# ice_header_adapter_pcb.net
KiCad netlist of a schematic drawn in EAGLE
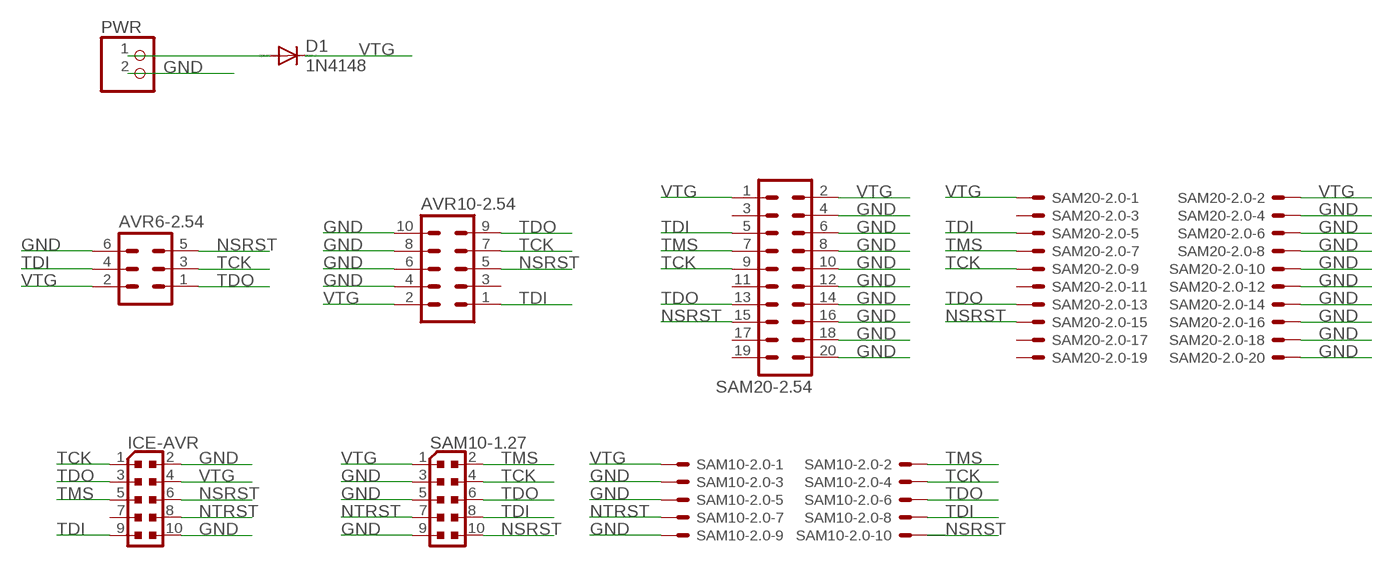
[diagram p0: schematic, sheet 1]

(export (version "E")
  (design (tool "Eeschema 10.0.6"))
  (components
    (comp (ref "AVR6-2.54")
      (value "ML6")
      (footprint "eagle-import:ML6")
      (libsource (lib "eagle-import") (part "ML6"))
    )
    (comp (ref "AVR10-2.54")
      (value "ML10")
      (footprint "eagle-import:ML10")
      (libsource (lib "eagle-import") (part "ML10"))
    )
    (comp (ref "D1")
      (value "1N4148")
      (footprint "eagle-import:DO35-7")
      (libsource (lib "eagle-import") (part "1N4148DO35-7"))
    )
    (comp (ref "ICE-AVR")
      (value "PINHEAD_PINHD-2X5PASSO127")
      (footprint "eagle-import:PINHEAD_2X05_127")
      (libsource (lib "eagle-import") (part "PINHEAD_PINHD-2X5PASSO127"))
    )
    (comp (ref "PWR")
      (value "PINHD-1X2/90")
      (footprint "eagle-import:1X02_90")
      (libsource (lib "eagle-import") (part "PINHD-1X2/90"))
    )
    (comp (ref "SAM10-1.27")
      (value "PINHEAD_PINHD-2X5PASSO127")
      (footprint "eagle-import:PINHEAD_2X05_127")
      (libsource (lib "eagle-import") (part "PINHEAD_PINHD-2X5PASSO127"))
    )
    (comp (ref "SAM10-2.0")
      (value "87758-1016")
      (footprint "eagle-import:87758-1016")
      (fields (field (name "MF") "MOLEX"))
      (libsource (lib "eagle-import") (part "87758-1016"))
    )
    (comp (ref "SAM20-2.0")
      (value "87758-2016")
      (footprint "eagle-import:87758-2016")
      (libsource (lib "eagle-import") (part "87758-2016"))
    )
    (comp (ref "SAM20-2.54")
      (value "ML20")
      (footprint "eagle-import:ML20")
      (libsource (lib "eagle-import") (part "ML20"))
    )
  )
  (nets
    (net (code "1") (name "/GND") (class "Default")
      (node (ref "AVR10-2.54") (pin "10") (pinfunction "10_10") (pintype "passive"))
      (node (ref "AVR10-2.54") (pin "4") (pinfunction "4_4") (pintype "passive"))
      (node (ref "AVR10-2.54") (pin "6") (pinfunction "6_6") (pintype "passive"))
      (node (ref "AVR10-2.54") (pin "8") (pinfunction "8_8") (pintype "passive"))
      (node (ref "AVR6-2.54") (pin "6") (pinfunction "6_6") (pintype "passive"))
      (node (ref "ICE-AVR") (pin "10") (pinfunction "10_10") (pintype "passive"))
      (node (ref "ICE-AVR") (pin "2") (pinfunction "2_2") (pintype "passive"))
      (node (ref "PWR") (pin "2") (pinfunction "2_2") (pintype "passive"))
      (node (ref "SAM10-1.27") (pin "3") (pinfunction "3_3") (pintype "passive"))
      (node (ref "SAM10-1.27") (pin "5") (pinfunction "5_5") (pintype "passive"))
      (node (ref "SAM10-1.27") (pin "9") (pinfunction "9_9") (pintype "passive"))
      (node (ref "SAM10-2.0") (pin "3") (pinfunction "S_3") (pintype "passive"))
      (node (ref "SAM10-2.0") (pin "5") (pinfunction "S_5") (pintype "passive"))
      (node (ref "SAM10-2.0") (pin "9") (pinfunction "S_9") (pintype "passive"))
      (node (ref "SAM20-2.0") (pin "10") (pinfunction "S_10") (pintype "passive"))
      (node (ref "SAM20-2.0") (pin "12") (pinfunction "S_12") (pintype "passive"))
      (node (ref "SAM20-2.0") (pin "14") (pinfunction "S_14") (pintype "passive"))
      (node (ref "SAM20-2.0") (pin "16") (pinfunction "S_16") (pintype "passive"))
      (node (ref "SAM20-2.0") (pin "18") (pinfunction "S_18") (pintype "passive"))
      (node (ref "SAM20-2.0") (pin "20") (pinfunction "S_20") (pintype "passive"))
      (node (ref "SAM20-2.0") (pin "4") (pinfunction "S_4") (pintype "passive"))
      (node (ref "SAM20-2.0") (pin "6") (pinfunction "S_6") (pintype "passive"))
      (node (ref "SAM20-2.0") (pin "8") (pinfunction "S_8") (pintype "passive"))
      (node (ref "SAM20-2.54") (pin "10") (pinfunction "10_10") (pintype "passive"))
      (node (ref "SAM20-2.54") (pin "12") (pinfunction "12_12") (pintype "passive"))
      (node (ref "SAM20-2.54") (pin "14") (pinfunction "14_14") (pintype "passive"))
      (node (ref "SAM20-2.54") (pin "16") (pinfunction "16_16") (pintype "passive"))
      (node (ref "SAM20-2.54") (pin "18") (pinfunction "18_18") (pintype "passive"))
      (node (ref "SAM20-2.54") (pin "20") (pinfunction "20_20") (pintype "passive"))
      (node (ref "SAM20-2.54") (pin "4") (pinfunction "4_4") (pintype "passive"))
      (node (ref "SAM20-2.54") (pin "6") (pinfunction "6_6") (pintype "passive"))
      (node (ref "SAM20-2.54") (pin "8") (pinfunction "8_8") (pintype "passive"))
    )
    (net (code "2") (name "/NSRST") (class "Default")
      (node (ref "AVR10-2.54") (pin "5") (pinfunction "5_5") (pintype "passive"))
      (node (ref "AVR6-2.54") (pin "5") (pinfunction "5_5") (pintype "passive"))
      (node (ref "ICE-AVR") (pin "6") (pinfunction "6_6") (pintype "passive"))
      (node (ref "SAM10-1.27") (pin "10") (pinfunction "10_10") (pintype "passive"))
      (node (ref "SAM10-2.0") (pin "10") (pinfunction "S_10") (pintype "passive"))
      (node (ref "SAM20-2.0") (pin "15") (pinfunction "S_15") (pintype "passive"))
      (node (ref "SAM20-2.54") (pin "15") (pinfunction "15_15") (pintype "passive"))
    )
    (net (code "3") (name "/NTRST") (class "Default")
      (node (ref "ICE-AVR") (pin "8") (pinfunction "8_8") (pintype "passive"))
      (node (ref "SAM10-1.27") (pin "7") (pinfunction "7_7") (pintype "passive"))
      (node (ref "SAM10-2.0") (pin "7") (pinfunction "S_7") (pintype "passive"))
    )
    (net (code "4") (name "/TCK") (class "Default")
      (node (ref "AVR10-2.54") (pin "7") (pinfunction "7_7") (pintype "passive"))
      (node (ref "AVR6-2.54") (pin "3") (pinfunction "3_3") (pintype "passive"))
      (node (ref "ICE-AVR") (pin "1") (pinfunction "1_1") (pintype "passive"))
      (node (ref "SAM10-1.27") (pin "4") (pinfunction "4_4") (pintype "passive"))
      (node (ref "SAM10-2.0") (pin "4") (pinfunction "S_4") (pintype "passive"))
      (node (ref "SAM20-2.0") (pin "9") (pinfunction "S_9") (pintype "passive"))
      (node (ref "SAM20-2.54") (pin "9") (pinfunction "9_9") (pintype "passive"))
    )
    (net (code "5") (name "/TDI") (class "Default")
      (node (ref "AVR10-2.54") (pin "1") (pinfunction "1_1") (pintype "passive"))
      (node (ref "AVR6-2.54") (pin "4") (pinfunction "4_4") (pintype "passive"))
      (node (ref "ICE-AVR") (pin "9") (pinfunction "9_9") (pintype "passive"))
      (node (ref "SAM10-1.27") (pin "8") (pinfunction "8_8") (pintype "passive"))
      (node (ref "SAM10-2.0") (pin "8") (pinfunction "S_8") (pintype "passive"))
      (node (ref "SAM20-2.0") (pin "5") (pinfunction "S_5") (pintype "passive"))
      (node (ref "SAM20-2.54") (pin "5") (pinfunction "5_5") (pintype "passive"))
    )
    (net (code "6") (name "/TDO") (class "Default")
      (node (ref "AVR10-2.54") (pin "9") (pinfunction "9_9") (pintype "passive"))
      (node (ref "AVR6-2.54") (pin "1") (pinfunction "1_1") (pintype "passive"))
      (node (ref "ICE-AVR") (pin "3") (pinfunction "3_3") (pintype "passive"))
      (node (ref "SAM10-1.27") (pin "6") (pinfunction "6_6") (pintype "passive"))
      (node (ref "SAM10-2.0") (pin "6") (pinfunction "S_6") (pintype "passive"))
      (node (ref "SAM20-2.0") (pin "13") (pinfunction "S_13") (pintype "passive"))
      (node (ref "SAM20-2.54") (pin "13") (pinfunction "13_13") (pintype "passive"))
    )
    (net (code "7") (name "/TMS") (class "Default")
      (node (ref "ICE-AVR") (pin "5") (pinfunction "5_5") (pintype "passive"))
      (node (ref "SAM10-1.27") (pin "2") (pinfunction "2_2") (pintype "passive"))
      (node (ref "SAM10-2.0") (pin "2") (pinfunction "S_2") (pintype "passive"))
      (node (ref "SAM20-2.0") (pin "7") (pinfunction "S_7") (pintype "passive"))
      (node (ref "SAM20-2.54") (pin "7") (pinfunction "7_7") (pintype "passive"))
    )
    (net (code "8") (name "/VTG") (class "Default")
      (node (ref "AVR10-2.54") (pin "2") (pinfunction "2_2") (pintype "passive"))
      (node (ref "AVR6-2.54") (pin "2") (pinfunction "2_2") (pintype "passive"))
      (node (ref "D1") (pin "C") (pinfunction "C_C") (pintype "passive"))
      (node (ref "ICE-AVR") (pin "4") (pinfunction "4_4") (pintype "passive"))
      (node (ref "SAM10-1.27") (pin "1") (pinfunction "1_1") (pintype "passive"))
      (node (ref "SAM10-2.0") (pin "1") (pinfunction "S_1") (pintype "passive"))
      (node (ref "SAM20-2.0") (pin "1") (pinfunction "S_1") (pintype "passive"))
      (node (ref "SAM20-2.0") (pin "2") (pinfunction "S_2") (pintype "passive"))
      (node (ref "SAM20-2.54") (pin "1") (pinfunction "1_1") (pintype "passive"))
      (node (ref "SAM20-2.54") (pin "2") (pinfunction "2_2") (pintype "passive"))
    )
    (net (code "9") (name "Net-(D1-PadA)") (class "Default")
      (node (ref "D1") (pin "A") (pinfunction "A_A") (pintype "passive"))
      (node (ref "PWR") (pin "1") (pinfunction "1_1") (pintype "passive"))
    )
    (net (code "10") (name "unconnected-(AVR10-2.54-Pad3)") (class "Default")
      (node (ref "AVR10-2.54") (pin "3") (pinfunction "3_3") (pintype "passive"))
    )
    (net (code "11") (name "unconnected-(ICE-AVR-Pad7)") (class "Default")
      (node (ref "ICE-AVR") (pin "7") (pinfunction "7_7") (pintype "passive"))
    )
    (net (code "12") (name "unconnected-(SAM20-2.0C-S-Pad11)") (class "Default")
      (node (ref "SAM20-2.0") (pin "11") (pinfunction "S_11") (pintype "passive"))
    )
    (net (code "13") (name "unconnected-(SAM20-2.0I-S-Pad17)") (class "Default")
      (node (ref "SAM20-2.0") (pin "17") (pinfunction "S_17") (pintype "passive"))
    )
    (net (code "14") (name "unconnected-(SAM20-2.0K-S-Pad19)") (class "Default")
      (node (ref "SAM20-2.0") (pin "19") (pinfunction "S_19") (pintype "passive"))
    )
    (net (code "15") (name "unconnected-(SAM20-2.0N-S-Pad3)") (class "Default")
      (node (ref "SAM20-2.0") (pin "3") (pinfunction "S_3") (pintype "passive"))
    )
    (net (code "16") (name "unconnected-(SAM20-2.54-Pad3)") (class "Default")
      (node (ref "SAM20-2.54") (pin "3") (pinfunction "3_3") (pintype "passive"))
    )
    (net (code "17") (name "unconnected-(SAM20-2.54-Pad11)") (class "Default")
      (node (ref "SAM20-2.54") (pin "11") (pinfunction "11_11") (pintype "passive"))
    )
    (net (code "18") (name "unconnected-(SAM20-2.54-Pad17)") (class "Default")
      (node (ref "SAM20-2.54") (pin "17") (pinfunction "17_17") (pintype "passive"))
    )
    (net (code "19") (name "unconnected-(SAM20-2.54-Pad19)") (class "Default")
      (node (ref "SAM20-2.54") (pin "19") (pinfunction "19_19") (pintype "passive"))
    )
  )
)
